# Precision_LPC_no_USB.net
KiCad netlist of a schematic drawn in EAGLE
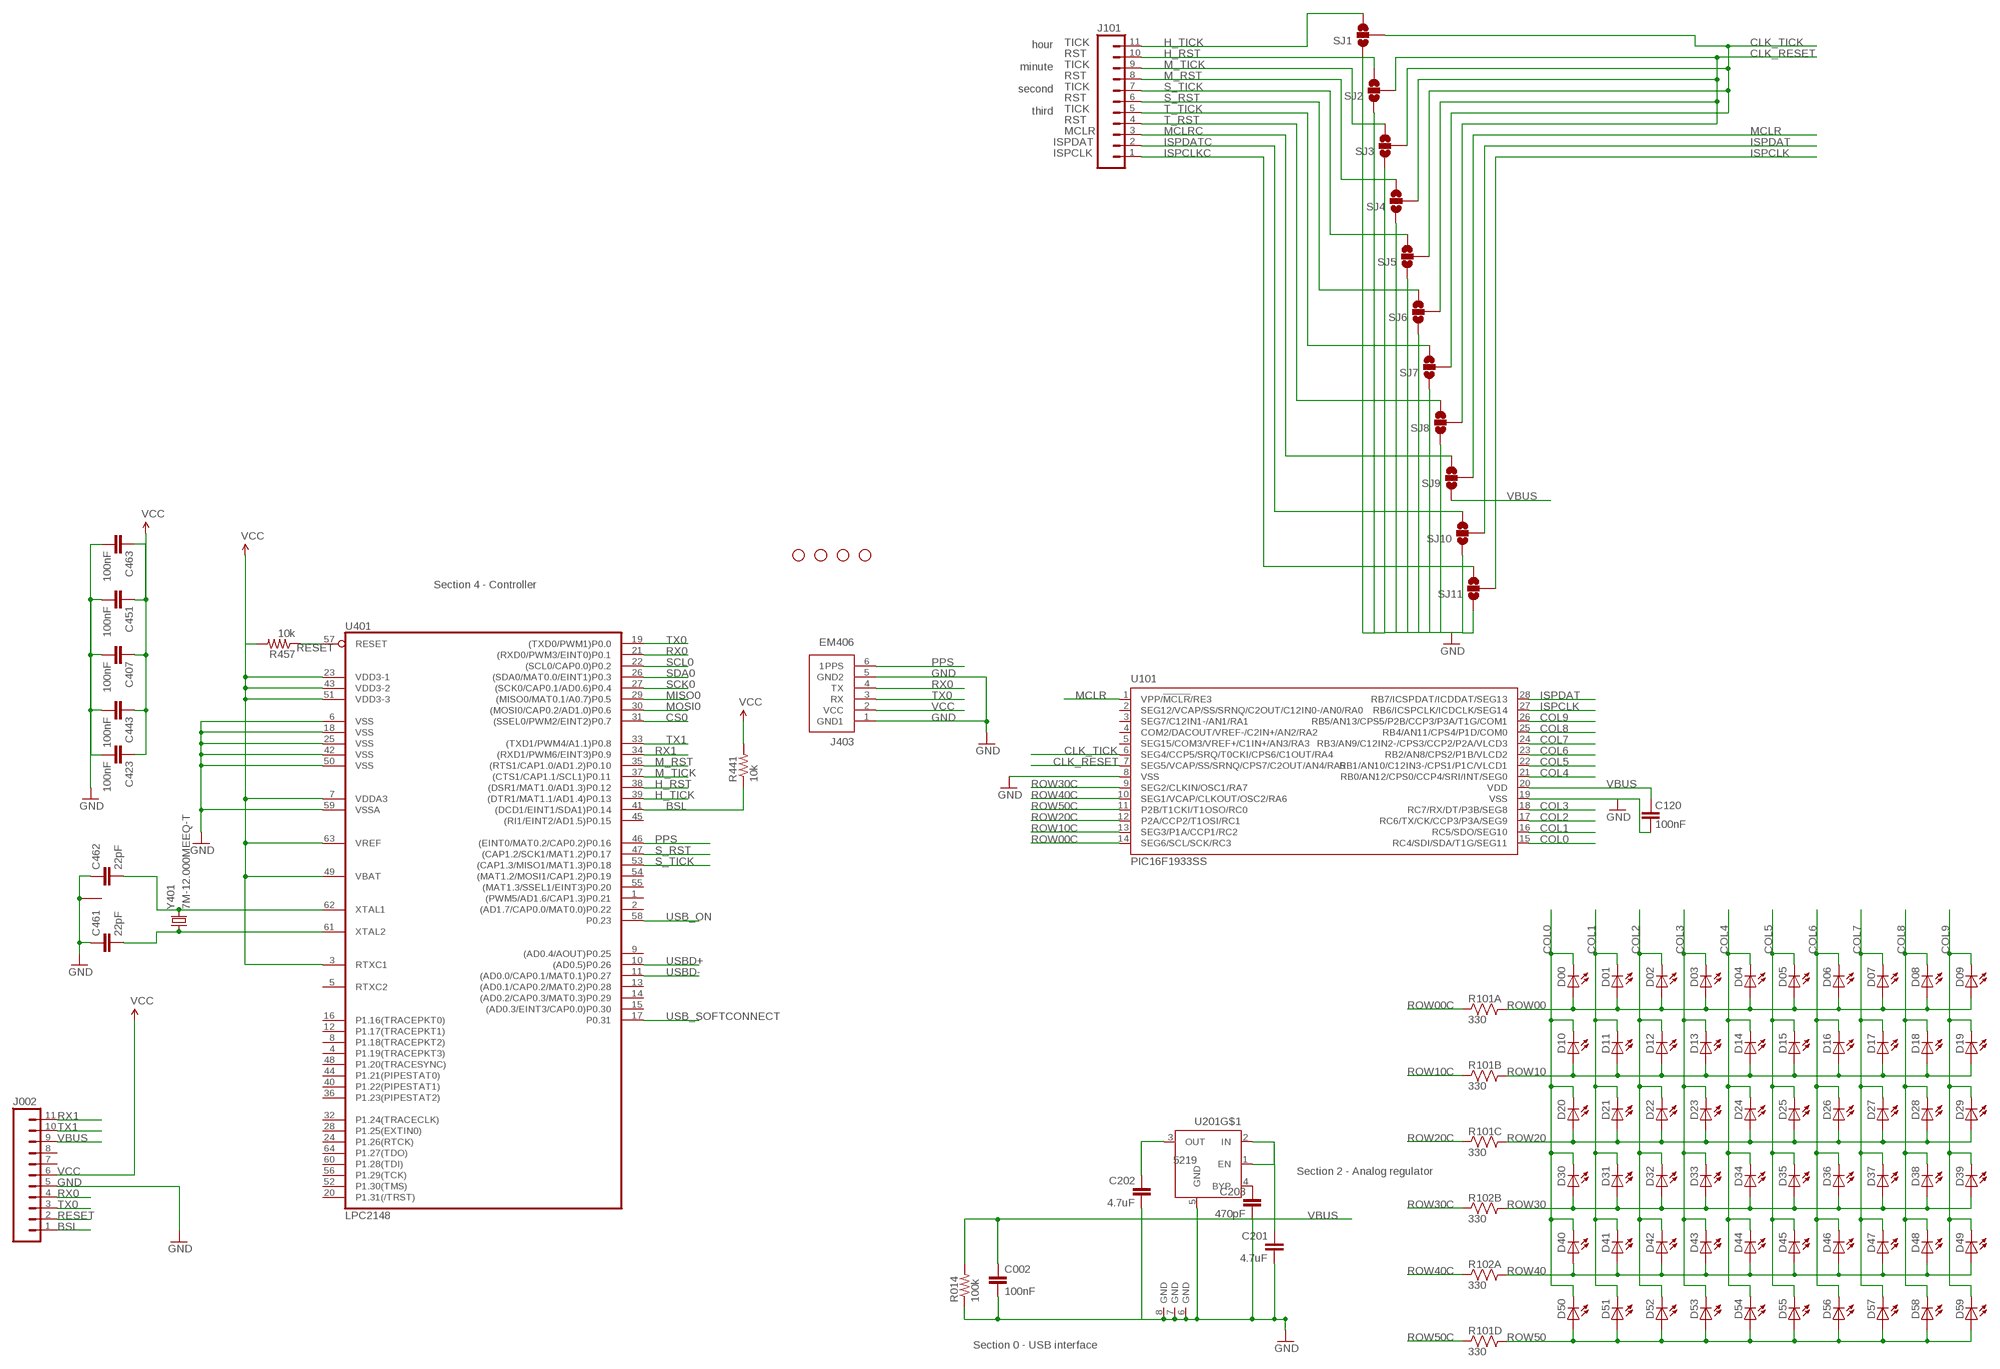
[diagram p0: schematic, sheet 1]

(export (version "E")
  (design (tool "Eeschema 10.0.6"))
  (components
    (comp (ref "C002")
      (value "100nF")
      (footprint "eagle-import:0402-CAP")
      (libsource (lib "eagle-import") (part "CAP0402-CAP"))
    )
    (comp (ref "C120")
      (value "100nF")
      (footprint "eagle-import:0402-CAP")
      (libsource (lib "eagle-import") (part "CAP0402-CAP"))
    )
    (comp (ref "C201")
      (value "4.7uF")
      (footprint "eagle-import:0402-CAP")
      (libsource (lib "eagle-import") (part "CAP0402-CAP"))
    )
    (comp (ref "C202")
      (value "4.7uF")
      (footprint "eagle-import:0402-CAP")
      (libsource (lib "eagle-import") (part "CAP0402-CAP"))
    )
    (comp (ref "C203")
      (value "470pF")
      (footprint "eagle-import:0402-CAP")
      (libsource (lib "eagle-import") (part "CAP0402-CAP"))
    )
    (comp (ref "C407")
      (value "100nF")
      (footprint "eagle-import:0402-CAP")
      (libsource (lib "eagle-import") (part "CAP0402-CAP"))
    )
    (comp (ref "C423")
      (value "100nF")
      (footprint "eagle-import:0402-CAP")
      (libsource (lib "eagle-import") (part "CAP0402-CAP"))
    )
    (comp (ref "C443")
      (value "100nF")
      (footprint "eagle-import:0402-CAP")
      (libsource (lib "eagle-import") (part "CAP0402-CAP"))
    )
    (comp (ref "C451")
      (value "100nF")
      (footprint "eagle-import:0402-CAP")
      (libsource (lib "eagle-import") (part "CAP0402-CAP"))
    )
    (comp (ref "C461")
      (value "22pF")
      (footprint "eagle-import:0402-CAP")
      (libsource (lib "eagle-import") (part "CAP0402-CAP"))
    )
    (comp (ref "C462")
      (value "22pF")
      (footprint "eagle-import:0402-CAP")
      (libsource (lib "eagle-import") (part "CAP0402-CAP"))
    )
    (comp (ref "C463")
      (value "100nF")
      (footprint "eagle-import:0402-CAP")
      (libsource (lib "eagle-import") (part "CAP0402-CAP"))
    )
    (comp (ref "D00")
      (value "LED3MM")
      (footprint "eagle-import:LED3MM")
      (libsource (lib "eagle-import") (part "LED3MM"))
    )
    (comp (ref "D01")
      (value "LED3MM")
      (footprint "eagle-import:LED3MM")
      (libsource (lib "eagle-import") (part "LED3MM"))
    )
    (comp (ref "D02")
      (value "LED3MM")
      (footprint "eagle-import:LED3MM")
      (libsource (lib "eagle-import") (part "LED3MM"))
    )
    (comp (ref "D03")
      (value "LED3MM")
      (footprint "eagle-import:LED3MM")
      (libsource (lib "eagle-import") (part "LED3MM"))
    )
    (comp (ref "D04")
      (value "LED3MM")
      (footprint "eagle-import:LED3MM")
      (libsource (lib "eagle-import") (part "LED3MM"))
    )
    (comp (ref "D05")
      (value "LED3MM")
      (footprint "eagle-import:LED3MM")
      (libsource (lib "eagle-import") (part "LED3MM"))
    )
    (comp (ref "D06")
      (value "LED3MM")
      (footprint "eagle-import:LED3MM")
      (libsource (lib "eagle-import") (part "LED3MM"))
    )
    (comp (ref "D07")
      (value "LED3MM")
      (footprint "eagle-import:LED3MM")
      (libsource (lib "eagle-import") (part "LED3MM"))
    )
    (comp (ref "D08")
      (value "LED3MM")
      (footprint "eagle-import:LED3MM")
      (libsource (lib "eagle-import") (part "LED3MM"))
    )
    (comp (ref "D09")
      (value "LED3MM")
      (footprint "eagle-import:LED3MM")
      (libsource (lib "eagle-import") (part "LED3MM"))
    )
    (comp (ref "D10")
      (value "LED3MM")
      (footprint "eagle-import:LED3MM")
      (libsource (lib "eagle-import") (part "LED3MM"))
    )
    (comp (ref "D11")
      (value "LED3MM")
      (footprint "eagle-import:LED3MM")
      (libsource (lib "eagle-import") (part "LED3MM"))
    )
    (comp (ref "D12")
      (value "LED3MM")
      (footprint "eagle-import:LED3MM")
      (libsource (lib "eagle-import") (part "LED3MM"))
    )
    (comp (ref "D13")
      (value "LED3MM")
      (footprint "eagle-import:LED3MM")
      (libsource (lib "eagle-import") (part "LED3MM"))
    )
    (comp (ref "D14")
      (value "LED3MM")
      (footprint "eagle-import:LED3MM")
      (libsource (lib "eagle-import") (part "LED3MM"))
    )
    (comp (ref "D15")
      (value "LED3MM")
      (footprint "eagle-import:LED3MM")
      (libsource (lib "eagle-import") (part "LED3MM"))
    )
    (comp (ref "D16")
      (value "LED3MM")
      (footprint "eagle-import:LED3MM")
      (libsource (lib "eagle-import") (part "LED3MM"))
    )
    (comp (ref "D17")
      (value "LED3MM")
      (footprint "eagle-import:LED3MM")
      (libsource (lib "eagle-import") (part "LED3MM"))
    )
    (comp (ref "D18")
      (value "LED3MM")
      (footprint "eagle-import:LED3MM")
      (libsource (lib "eagle-import") (part "LED3MM"))
    )
    (comp (ref "D19")
      (value "LED3MM")
      (footprint "eagle-import:LED3MM")
      (libsource (lib "eagle-import") (part "LED3MM"))
    )
    (comp (ref "D20")
      (value "LED3MM")
      (footprint "eagle-import:LED3MM")
      (libsource (lib "eagle-import") (part "LED3MM"))
    )
    (comp (ref "D21")
      (value "LED3MM")
      (footprint "eagle-import:LED3MM")
      (libsource (lib "eagle-import") (part "LED3MM"))
    )
    (comp (ref "D22")
      (value "LED3MM")
      (footprint "eagle-import:LED3MM")
      (libsource (lib "eagle-import") (part "LED3MM"))
    )
    (comp (ref "D23")
      (value "LED3MM")
      (footprint "eagle-import:LED3MM")
      (libsource (lib "eagle-import") (part "LED3MM"))
    )
    (comp (ref "D24")
      (value "LED3MM")
      (footprint "eagle-import:LED3MM")
      (libsource (lib "eagle-import") (part "LED3MM"))
    )
    (comp (ref "D25")
      (value "LED3MM")
      (footprint "eagle-import:LED3MM")
      (libsource (lib "eagle-import") (part "LED3MM"))
    )
    (comp (ref "D26")
      (value "LED3MM")
      (footprint "eagle-import:LED3MM")
      (libsource (lib "eagle-import") (part "LED3MM"))
    )
    (comp (ref "D27")
      (value "LED3MM")
      (footprint "eagle-import:LED3MM")
      (libsource (lib "eagle-import") (part "LED3MM"))
    )
    (comp (ref "D28")
      (value "LED3MM")
      (footprint "eagle-import:LED3MM")
      (libsource (lib "eagle-import") (part "LED3MM"))
    )
    (comp (ref "D29")
      (value "LED3MM")
      (footprint "eagle-import:LED3MM")
      (libsource (lib "eagle-import") (part "LED3MM"))
    )
    (comp (ref "D30")
      (value "LED3MM")
      (footprint "eagle-import:LED3MM")
      (libsource (lib "eagle-import") (part "LED3MM"))
    )
    (comp (ref "D31")
      (value "LED3MM")
      (footprint "eagle-import:LED3MM")
      (libsource (lib "eagle-import") (part "LED3MM"))
    )
    (comp (ref "D32")
      (value "LED3MM")
      (footprint "eagle-import:LED3MM")
      (libsource (lib "eagle-import") (part "LED3MM"))
    )
    (comp (ref "D33")
      (value "LED3MM")
      (footprint "eagle-import:LED3MM")
      (libsource (lib "eagle-import") (part "LED3MM"))
    )
    (comp (ref "D34")
      (value "LED3MM")
      (footprint "eagle-import:LED3MM")
      (libsource (lib "eagle-import") (part "LED3MM"))
    )
    (comp (ref "D35")
      (value "LED3MM")
      (footprint "eagle-import:LED3MM")
      (libsource (lib "eagle-import") (part "LED3MM"))
    )
    (comp (ref "D36")
      (value "LED3MM")
      (footprint "eagle-import:LED3MM")
      (libsource (lib "eagle-import") (part "LED3MM"))
    )
    (comp (ref "D37")
      (value "LED3MM")
      (footprint "eagle-import:LED3MM")
      (libsource (lib "eagle-import") (part "LED3MM"))
    )
    (comp (ref "D38")
      (value "LED3MM")
      (footprint "eagle-import:LED3MM")
      (libsource (lib "eagle-import") (part "LED3MM"))
    )
    (comp (ref "D39")
      (value "LED3MM")
      (footprint "eagle-import:LED3MM")
      (libsource (lib "eagle-import") (part "LED3MM"))
    )
    (comp (ref "D40")
      (value "LED3MM")
      (footprint "eagle-import:LED3MM")
      (libsource (lib "eagle-import") (part "LED3MM"))
    )
    (comp (ref "D41")
      (value "LED3MM")
      (footprint "eagle-import:LED3MM")
      (libsource (lib "eagle-import") (part "LED3MM"))
    )
    (comp (ref "D42")
      (value "LED3MM")
      (footprint "eagle-import:LED3MM")
      (libsource (lib "eagle-import") (part "LED3MM"))
    )
    (comp (ref "D43")
      (value "LED3MM")
      (footprint "eagle-import:LED3MM")
      (libsource (lib "eagle-import") (part "LED3MM"))
    )
    (comp (ref "D44")
      (value "LED3MM")
      (footprint "eagle-import:LED3MM")
      (libsource (lib "eagle-import") (part "LED3MM"))
    )
    (comp (ref "D45")
      (value "LED3MM")
      (footprint "eagle-import:LED3MM")
      (libsource (lib "eagle-import") (part "LED3MM"))
    )
    (comp (ref "D46")
      (value "LED3MM")
      (footprint "eagle-import:LED3MM")
      (libsource (lib "eagle-import") (part "LED3MM"))
    )
    (comp (ref "D47")
      (value "LED3MM")
      (footprint "eagle-import:LED3MM")
      (libsource (lib "eagle-import") (part "LED3MM"))
    )
    (comp (ref "D48")
      (value "LED3MM")
      (footprint "eagle-import:LED3MM")
      (libsource (lib "eagle-import") (part "LED3MM"))
    )
    (comp (ref "D49")
      (value "LED3MM")
      (footprint "eagle-import:LED3MM")
      (libsource (lib "eagle-import") (part "LED3MM"))
    )
    (comp (ref "D50")
      (value "LED3MM")
      (footprint "eagle-import:LED3MM")
      (libsource (lib "eagle-import") (part "LED3MM"))
    )
    (comp (ref "D51")
      (value "LED3MM")
      (footprint "eagle-import:LED3MM")
      (libsource (lib "eagle-import") (part "LED3MM"))
    )
    (comp (ref "D52")
      (value "LED3MM")
      (footprint "eagle-import:LED3MM")
      (libsource (lib "eagle-import") (part "LED3MM"))
    )
    (comp (ref "D53")
      (value "LED3MM")
      (footprint "eagle-import:LED3MM")
      (libsource (lib "eagle-import") (part "LED3MM"))
    )
    (comp (ref "D54")
      (value "LED3MM")
      (footprint "eagle-import:LED3MM")
      (libsource (lib "eagle-import") (part "LED3MM"))
    )
    (comp (ref "D55")
      (value "LED3MM")
      (footprint "eagle-import:LED3MM")
      (libsource (lib "eagle-import") (part "LED3MM"))
    )
    (comp (ref "D56")
      (value "LED3MM")
      (footprint "eagle-import:LED3MM")
      (libsource (lib "eagle-import") (part "LED3MM"))
    )
    (comp (ref "D57")
      (value "LED3MM")
      (footprint "eagle-import:LED3MM")
      (libsource (lib "eagle-import") (part "LED3MM"))
    )
    (comp (ref "D58")
      (value "LED3MM")
      (footprint "eagle-import:LED3MM")
      (libsource (lib "eagle-import") (part "LED3MM"))
    )
    (comp (ref "D59")
      (value "LED3MM")
      (footprint "eagle-import:LED3MM")
      (libsource (lib "eagle-import") (part "LED3MM"))
    )
    (comp (ref "J002")
      (value "M11PTH")
      (footprint "eagle-import:1X11")
      (libsource (lib "eagle-import") (part "M11PTH"))
    )
    (comp (ref "J101")
      (value "M11PTH")
      (footprint "eagle-import:1X11")
      (libsource (lib "eagle-import") (part "M11PTH"))
    )
    (comp (ref "J403")
      (value "EM406")
      (footprint "eagle-import:EM406@1")
      (libsource (lib "eagle-import") (part "EM406"))
    )
    (comp (ref "JP3")
      (value "STAND-OFF")
      (footprint "eagle-import:STAND-OFF")
      (libsource (lib "eagle-import") (part "STAND-OFF"))
    )
    (comp (ref "JP4")
      (value "STAND-OFF")
      (footprint "eagle-import:STAND-OFF")
      (libsource (lib "eagle-import") (part "STAND-OFF"))
    )
    (comp (ref "JP5")
      (value "STAND-OFF")
      (footprint "eagle-import:STAND-OFF")
      (libsource (lib "eagle-import") (part "STAND-OFF"))
    )
    (comp (ref "JP6")
      (value "STAND-OFF")
      (footprint "eagle-import:STAND-OFF")
      (libsource (lib "eagle-import") (part "STAND-OFF"))
    )
    (comp (ref "R014")
      (value "100k")
      (footprint "eagle-import:0402-RES")
      (libsource (lib "eagle-import") (part "RESISTOR0402-RES"))
    )
    (comp (ref "R101")
      (value "330")
      (footprint "eagle-import:CRA06")
      (libsource (lib "eagle-import") (part "CRA06S-8"))
    )
    (comp (ref "R102")
      (value "330")
      (footprint "eagle-import:CRA06")
      (libsource (lib "eagle-import") (part "CRA06S-8"))
    )
    (comp (ref "R441")
      (value "10k")
      (footprint "eagle-import:0402-RES")
      (libsource (lib "eagle-import") (part "RESISTOR0402-RES"))
    )
    (comp (ref "R457")
      (value "10k")
      (footprint "eagle-import:0402-RES")
      (libsource (lib "eagle-import") (part "RESISTOR0402-RES"))
    )
    (comp (ref "SJ1")
      (value "SOLDERJUMPER_2WAYS")
      (footprint "eagle-import:SJ_3")
      (libsource (lib "eagle-import") (part "SOLDERJUMPER_2WAYS"))
    )
    (comp (ref "SJ2")
      (value "SOLDERJUMPER_2WAYS")
      (footprint "eagle-import:SJ_3")
      (libsource (lib "eagle-import") (part "SOLDERJUMPER_2WAYS"))
    )
    (comp (ref "SJ3")
      (value "SOLDERJUMPER_2WAYS")
      (footprint "eagle-import:SJ_3")
      (libsource (lib "eagle-import") (part "SOLDERJUMPER_2WAYS"))
    )
    (comp (ref "SJ4")
      (value "SOLDERJUMPER_2WAYS")
      (footprint "eagle-import:SJ_3")
      (libsource (lib "eagle-import") (part "SOLDERJUMPER_2WAYS"))
    )
    (comp (ref "SJ5")
      (value "SOLDERJUMPER_2WAYS")
      (footprint "eagle-import:SJ_3")
      (libsource (lib "eagle-import") (part "SOLDERJUMPER_2WAYS"))
    )
    (comp (ref "SJ6")
      (value "SOLDERJUMPER_2WAYS")
      (footprint "eagle-import:SJ_3")
      (libsource (lib "eagle-import") (part "SOLDERJUMPER_2WAYS"))
    )
    (comp (ref "SJ7")
      (value "SOLDERJUMPER_2WAYS")
      (footprint "eagle-import:SJ_3")
      (libsource (lib "eagle-import") (part "SOLDERJUMPER_2WAYS"))
    )
    (comp (ref "SJ8")
      (value "SOLDERJUMPER_2WAYS")
      (footprint "eagle-import:SJ_3")
      (libsource (lib "eagle-import") (part "SOLDERJUMPER_2WAYS"))
    )
    (comp (ref "SJ9")
      (value "SOLDERJUMPER_2WAYS")
      (footprint "eagle-import:SJ_3")
      (libsource (lib "eagle-import") (part "SOLDERJUMPER_2WAYS"))
    )
    (comp (ref "SJ10")
      (value "SOLDERJUMPER_2WAYS")
      (footprint "eagle-import:SJ_3")
      (libsource (lib "eagle-import") (part "SOLDERJUMPER_2WAYS"))
    )
    (comp (ref "SJ11")
      (value "SOLDERJUMPER_2WAYS")
      (footprint "eagle-import:SJ_3")
      (libsource (lib "eagle-import") (part "SOLDERJUMPER_2WAYS"))
    )
    (comp (ref "U101")
      (value "PIC16F1933SS")
      (footprint "eagle-import:SSOP28")
      (fields (field (name "MPN") "PIC16F1933T-I/SS"))
      (libsource (lib "eagle-import") (part "PIC16F19SS33"))
    )
    (comp (ref "U201")
      (value "5219")
      (footprint "eagle-import:MSOP08")
      (libsource (lib "eagle-import") (part "MIC5219FMM"))
    )
    (comp (ref "U401")
      (value "LPC2148")
      (footprint "eagle-import:SQFP-S-10X10-64")
      (libsource (lib "eagle-import") (part "LPC213X"))
    )
    (comp (ref "Y401")
      (value "7M-12.000MEEQ-T")
      (footprint "eagle-import:CRYSTAL_SMD")
      (libsource (lib "eagle-import") (part "TSX-3225"))
    )
  )
  (nets
    (net (code "1") (name "/BSL") (class "Default")
      (node (ref "J002") (pin "1") (pinfunction "1_1") (pintype "passive"))
      (node (ref "R441") (pin "1") (pinfunction "1_1") (pintype "passive"))
      (node (ref "U401") (pin "41") (pinfunction "(DCD1/EINT1/SDA1)P0.14_41") (pintype "bidirectional"))
    )
    (net (code "2") (name "/CLK_RESET") (class "Default")
      (node (ref "SJ2") (pin "2") (pinfunction "2_2") (pintype "passive"))
      (node (ref "SJ4") (pin "2") (pinfunction "2_2") (pintype "passive"))
      (node (ref "SJ6") (pin "2") (pinfunction "2_2") (pintype "passive"))
      (node (ref "SJ8") (pin "2") (pinfunction "2_2") (pintype "passive"))
      (node (ref "U101") (pin "7") (pinfunction "SEG5/VCAP/SS/SRNQ/CPS7/C2OUT/AN4/RA5_7") (pintype "bidirectional"))
    )
    (net (code "3") (name "/CLK_TICK") (class "Default")
      (node (ref "SJ1") (pin "2") (pinfunction "2_2") (pintype "passive"))
      (node (ref "SJ3") (pin "2") (pinfunction "2_2") (pintype "passive"))
      (node (ref "SJ5") (pin "2") (pinfunction "2_2") (pintype "passive"))
      (node (ref "SJ7") (pin "2") (pinfunction "2_2") (pintype "passive"))
      (node (ref "U101") (pin "6") (pinfunction "SEG4/CCP5/SRQ/T0CKI/CPS6/C1OUT/RA4_6") (pintype "bidirectional"))
    )
    (net (code "4") (name "/COL0") (class "Default")
      (node (ref "D00") (pin "K") (pinfunction "C_K") (pintype "passive"))
      (node (ref "D10") (pin "K") (pinfunction "C_K") (pintype "passive"))
      (node (ref "D20") (pin "K") (pinfunction "C_K") (pintype "passive"))
      (node (ref "D30") (pin "K") (pinfunction "C_K") (pintype "passive"))
      (node (ref "D40") (pin "K") (pinfunction "C_K") (pintype "passive"))
      (node (ref "D50") (pin "K") (pinfunction "C_K") (pintype "passive"))
      (node (ref "U101") (pin "15") (pinfunction "RC4/SDI/SDA/T1G/SEG11_15") (pintype "bidirectional"))
    )
    (net (code "5") (name "/COL1") (class "Default")
      (node (ref "D01") (pin "K") (pinfunction "C_K") (pintype "passive"))
      (node (ref "D11") (pin "K") (pinfunction "C_K") (pintype "passive"))
      (node (ref "D21") (pin "K") (pinfunction "C_K") (pintype "passive"))
      (node (ref "D31") (pin "K") (pinfunction "C_K") (pintype "passive"))
      (node (ref "D41") (pin "K") (pinfunction "C_K") (pintype "passive"))
      (node (ref "D51") (pin "K") (pinfunction "C_K") (pintype "passive"))
      (node (ref "U101") (pin "16") (pinfunction "RC5/SDO/SEG10_16") (pintype "bidirectional"))
    )
    (net (code "6") (name "/COL2") (class "Default")
      (node (ref "D02") (pin "K") (pinfunction "C_K") (pintype "passive"))
      (node (ref "D12") (pin "K") (pinfunction "C_K") (pintype "passive"))
      (node (ref "D22") (pin "K") (pinfunction "C_K") (pintype "passive"))
      (node (ref "D32") (pin "K") (pinfunction "C_K") (pintype "passive"))
      (node (ref "D42") (pin "K") (pinfunction "C_K") (pintype "passive"))
      (node (ref "D52") (pin "K") (pinfunction "C_K") (pintype "passive"))
      (node (ref "U101") (pin "17") (pinfunction "RC6/TX/CK/CCP3/P3A/SEG9_17") (pintype "bidirectional"))
    )
    (net (code "7") (name "/COL3") (class "Default")
      (node (ref "D03") (pin "K") (pinfunction "C_K") (pintype "passive"))
      (node (ref "D13") (pin "K") (pinfunction "C_K") (pintype "passive"))
      (node (ref "D23") (pin "K") (pinfunction "C_K") (pintype "passive"))
      (node (ref "D33") (pin "K") (pinfunction "C_K") (pintype "passive"))
      (node (ref "D43") (pin "K") (pinfunction "C_K") (pintype "passive"))
      (node (ref "D53") (pin "K") (pinfunction "C_K") (pintype "passive"))
      (node (ref "U101") (pin "18") (pinfunction "RC7/RX/DT/P3B/SEG8_18") (pintype "bidirectional"))
    )
    (net (code "8") (name "/COL4") (class "Default")
      (node (ref "D04") (pin "K") (pinfunction "C_K") (pintype "passive"))
      (node (ref "D14") (pin "K") (pinfunction "C_K") (pintype "passive"))
      (node (ref "D24") (pin "K") (pinfunction "C_K") (pintype "passive"))
      (node (ref "D34") (pin "K") (pinfunction "C_K") (pintype "passive"))
      (node (ref "D44") (pin "K") (pinfunction "C_K") (pintype "passive"))
      (node (ref "D54") (pin "K") (pinfunction "C_K") (pintype "passive"))
      (node (ref "U101") (pin "21") (pinfunction "RB0/AN12/CPS0/CCP4/SRI/INT/SEG0_21") (pintype "bidirectional"))
    )
    (net (code "9") (name "/COL5") (class "Default")
      (node (ref "D05") (pin "K") (pinfunction "C_K") (pintype "passive"))
      (node (ref "D15") (pin "K") (pinfunction "C_K") (pintype "passive"))
      (node (ref "D25") (pin "K") (pinfunction "C_K") (pintype "passive"))
      (node (ref "D35") (pin "K") (pinfunction "C_K") (pintype "passive"))
      (node (ref "D45") (pin "K") (pinfunction "C_K") (pintype "passive"))
      (node (ref "D55") (pin "K") (pinfunction "C_K") (pintype "passive"))
      (node (ref "U101") (pin "22") (pinfunction "RB1/AN10/C12IN3-/CPS1/P1C/VLCD1_22") (pintype "bidirectional"))
    )
    (net (code "10") (name "/COL6") (class "Default")
      (node (ref "D06") (pin "K") (pinfunction "C_K") (pintype "passive"))
      (node (ref "D16") (pin "K") (pinfunction "C_K") (pintype "passive"))
      (node (ref "D26") (pin "K") (pinfunction "C_K") (pintype "passive"))
      (node (ref "D36") (pin "K") (pinfunction "C_K") (pintype "passive"))
      (node (ref "D46") (pin "K") (pinfunction "C_K") (pintype "passive"))
      (node (ref "D56") (pin "K") (pinfunction "C_K") (pintype "passive"))
      (node (ref "U101") (pin "23") (pinfunction "RB2/AN8/CPS2/P1B/VLCD2_23") (pintype "bidirectional"))
    )
    (net (code "11") (name "/COL7") (class "Default")
      (node (ref "D07") (pin "K") (pinfunction "C_K") (pintype "passive"))
      (node (ref "D17") (pin "K") (pinfunction "C_K") (pintype "passive"))
      (node (ref "D27") (pin "K") (pinfunction "C_K") (pintype "passive"))
      (node (ref "D37") (pin "K") (pinfunction "C_K") (pintype "passive"))
      (node (ref "D47") (pin "K") (pinfunction "C_K") (pintype "passive"))
      (node (ref "D57") (pin "K") (pinfunction "C_K") (pintype "passive"))
      (node (ref "U101") (pin "24") (pinfunction "RB3/AN9/C12IN2-/CPS3/CCP2/P2A/VLCD3_24") (pintype "bidirectional"))
    )
    (net (code "12") (name "/COL8") (class "Default")
      (node (ref "D08") (pin "K") (pinfunction "C_K") (pintype "passive"))
      (node (ref "D18") (pin "K") (pinfunction "C_K") (pintype "passive"))
      (node (ref "D28") (pin "K") (pinfunction "C_K") (pintype "passive"))
      (node (ref "D38") (pin "K") (pinfunction "C_K") (pintype "passive"))
      (node (ref "D48") (pin "K") (pinfunction "C_K") (pintype "passive"))
      (node (ref "D58") (pin "K") (pinfunction "C_K") (pintype "passive"))
      (node (ref "U101") (pin "25") (pinfunction "RB4/AN11/CPS4/P1D/COM0_25") (pintype "bidirectional"))
    )
    (net (code "13") (name "/COL9") (class "Default")
      (node (ref "D09") (pin "K") (pinfunction "C_K") (pintype "passive"))
      (node (ref "D19") (pin "K") (pinfunction "C_K") (pintype "passive"))
      (node (ref "D29") (pin "K") (pinfunction "C_K") (pintype "passive"))
      (node (ref "D39") (pin "K") (pinfunction "C_K") (pintype "passive"))
      (node (ref "D49") (pin "K") (pinfunction "C_K") (pintype "passive"))
      (node (ref "D59") (pin "K") (pinfunction "C_K") (pintype "passive"))
      (node (ref "U101") (pin "26") (pinfunction "RB5/AN13/CPS5/P2B/CCP3/P3A/T1G/COM1_26") (pintype "bidirectional"))
    )
    (net (code "14") (name "/CS0") (class "Default")
      (node (ref "U401") (pin "31") (pinfunction "(SSEL0/PWM2/EINT2)P0.7_31") (pintype "bidirectional"))
    )
    (net (code "15") (name "/H_RST") (class "Default")
      (node (ref "J101") (pin "10") (pinfunction "10_10") (pintype "passive"))
      (node (ref "SJ2") (pin "3") (pinfunction "3_3") (pintype "passive"))
      (node (ref "U401") (pin "38") (pinfunction "(DSR1/MAT1.0/AD1.3)P0.12_38") (pintype "bidirectional"))
    )
    (net (code "16") (name "/H_TICK") (class "Default")
      (node (ref "J101") (pin "11") (pinfunction "11_11") (pintype "passive"))
      (node (ref "SJ1") (pin "3") (pinfunction "3_3") (pintype "passive"))
      (node (ref "U401") (pin "39") (pinfunction "(DTR1/MAT1.1/AD1.4)P0.13_39") (pintype "bidirectional"))
    )
    (net (code "17") (name "/ISPCLK") (class "Default")
      (node (ref "SJ11") (pin "2") (pinfunction "2_2") (pintype "passive"))
      (node (ref "U101") (pin "27") (pinfunction "RB6/ICSPCLK/ICDCLK/SEG14_27") (pintype "bidirectional"))
    )
    (net (code "18") (name "/ISPCLKC") (class "Default")
      (node (ref "J101") (pin "1") (pinfunction "1_1") (pintype "passive"))
      (node (ref "SJ11") (pin "3") (pinfunction "3_3") (pintype "passive"))
    )
    (net (code "19") (name "/ISPDAT") (class "Default")
      (node (ref "SJ10") (pin "2") (pinfunction "2_2") (pintype "passive"))
      (node (ref "U101") (pin "28") (pinfunction "RB7/ICSPDAT/ICDDAT/SEG13_28") (pintype "bidirectional"))
    )
    (net (code "20") (name "/ISPDATC") (class "Default")
      (node (ref "J101") (pin "2") (pinfunction "2_2") (pintype "passive"))
      (node (ref "SJ10") (pin "3") (pinfunction "3_3") (pintype "passive"))
    )
    (net (code "21") (name "/MCLR") (class "Default")
      (node (ref "SJ9") (pin "2") (pinfunction "2_2") (pintype "passive"))
      (node (ref "U101") (pin "1") (pinfunction "VPP/~{MCLR}/RE3_1") (pintype "input"))
    )
    (net (code "22") (name "/MCLRC") (class "Default")
      (node (ref "J101") (pin "3") (pinfunction "3_3") (pintype "passive"))
      (node (ref "SJ9") (pin "3") (pinfunction "3_3") (pintype "passive"))
    )
    (net (code "23") (name "/MISO0") (class "Default")
      (node (ref "U401") (pin "29") (pinfunction "(MISO0/MAT0.1/A0.7)P0.5_29") (pintype "bidirectional"))
    )
    (net (code "24") (name "/MOSI0") (class "Default")
      (node (ref "U401") (pin "30") (pinfunction "(MOSI0/CAP0.2/AD1.0)P0.6_30") (pintype "bidirectional"))
    )
    (net (code "25") (name "/M_RST") (class "Default")
      (node (ref "J101") (pin "8") (pinfunction "8_8") (pintype "passive"))
      (node (ref "SJ4") (pin "3") (pinfunction "3_3") (pintype "passive"))
      (node (ref "U401") (pin "35") (pinfunction "(RTS1/CAP1.0/AD1.2)P0.10_35") (pintype "bidirectional"))
    )
    (net (code "26") (name "/M_TICK") (class "Default")
      (node (ref "J101") (pin "9") (pinfunction "9_9") (pintype "passive"))
      (node (ref "SJ3") (pin "3") (pinfunction "3_3") (pintype "passive"))
      (node (ref "U401") (pin "37") (pinfunction "(CTS1/CAP1.1/SCL1)P0.11_37") (pintype "bidirectional"))
    )
    (net (code "27") (name "/PPS") (class "Default")
      (node (ref "J403") (pin "6") (pinfunction "1PPS_6") (pintype "bidirectional"))
      (node (ref "U401") (pin "46") (pinfunction "(EINT0/MAT0.2/CAP0.2)P0.16_46") (pintype "bidirectional"))
    )
    (net (code "28") (name "/RESET") (class "Default")
      (node (ref "J002") (pin "2") (pinfunction "2_2") (pintype "passive"))
      (node (ref "R457") (pin "1") (pinfunction "1_1") (pintype "passive"))
      (node (ref "U401") (pin "57") (pinfunction "RESET_57") (pintype "input"))
    )
    (net (code "29") (name "/ROW00") (class "Default")
      (node (ref "D00") (pin "A") (pinfunction "A_A") (pintype "passive"))
      (node (ref "D01") (pin "A") (pinfunction "A_A") (pintype "passive"))
      (node (ref "D02") (pin "A") (pinfunction "A_A") (pintype "passive"))
      (node (ref "D03") (pin "A") (pinfunction "A_A") (pintype "passive"))
      (node (ref "D04") (pin "A") (pinfunction "A_A") (pintype "passive"))
      (node (ref "D05") (pin "A") (pinfunction "A_A") (pintype "passive"))
      (node (ref "D06") (pin "A") (pinfunction "A_A") (pintype "passive"))
      (node (ref "D07") (pin "A") (pinfunction "A_A") (pintype "passive"))
      (node (ref "D08") (pin "A") (pinfunction "A_A") (pintype "passive"))
      (node (ref "D09") (pin "A") (pinfunction "A_A") (pintype "passive"))
      (node (ref "R101") (pin "8") (pinfunction "2_8") (pintype "passive"))
    )
    (net (code "30") (name "/ROW00C") (class "Default")
      (node (ref "R101") (pin "1") (pinfunction "1_1") (pintype "passive"))
      (node (ref "U101") (pin "14") (pinfunction "SEG6/SCL/SCK/RC3_14") (pintype "bidirectional"))
    )
    (net (code "31") (name "/ROW10") (class "Default")
      (node (ref "D10") (pin "A") (pinfunction "A_A") (pintype "passive"))
      (node (ref "D11") (pin "A") (pinfunction "A_A") (pintype "passive"))
      (node (ref "D12") (pin "A") (pinfunction "A_A") (pintype "passive"))
      (node (ref "D13") (pin "A") (pinfunction "A_A") (pintype "passive"))
      (node (ref "D14") (pin "A") (pinfunction "A_A") (pintype "passive"))
      (node (ref "D15") (pin "A") (pinfunction "A_A") (pintype "passive"))
      (node (ref "D16") (pin "A") (pinfunction "A_A") (pintype "passive"))
      (node (ref "D17") (pin "A") (pinfunction "A_A") (pintype "passive"))
      (node (ref "D18") (pin "A") (pinfunction "A_A") (pintype "passive"))
      (node (ref "D19") (pin "A") (pinfunction "A_A") (pintype "passive"))
      (node (ref "R101") (pin "7") (pinfunction "2_7") (pintype "passive"))
    )
    (net (code "32") (name "/ROW10C") (class "Default")
      (node (ref "R101") (pin "2") (pinfunction "1_2") (pintype "passive"))
      (node (ref "U101") (pin "13") (pinfunction "SEG3/P1A/CCP1/RC2_13") (pintype "bidirectional"))
    )
    (net (code "33") (name "/ROW20") (class "Default")
      (node (ref "D20") (pin "A") (pinfunction "A_A") (pintype "passive"))
      (node (ref "D21") (pin "A") (pinfunction "A_A") (pintype "passive"))
      (node (ref "D22") (pin "A") (pinfunction "A_A") (pintype "passive"))
      (node (ref "D23") (pin "A") (pinfunction "A_A") (pintype "passive"))
      (node (ref "D24") (pin "A") (pinfunction "A_A") (pintype "passive"))
      (node (ref "D25") (pin "A") (pinfunction "A_A") (pintype "passive"))
      (node (ref "D26") (pin "A") (pinfunction "A_A") (pintype "passive"))
      (node (ref "D27") (pin "A") (pinfunction "A_A") (pintype "passive"))
      (node (ref "D28") (pin "A") (pinfunction "A_A") (pintype "passive"))
      (node (ref "D29") (pin "A") (pinfunction "A_A") (pintype "passive"))
      (node (ref "R101") (pin "6") (pinfunction "2_6") (pintype "passive"))
    )
    (net (code "34") (name "/ROW20C") (class "Default")
      (node (ref "R101") (pin "3") (pinfunction "1_3") (pintype "passive"))
      (node (ref "U101") (pin "12") (pinfunction "P2A/CCP2/T1OSI/RC1_12") (pintype "bidirectional"))
    )
    (net (code "35") (name "/ROW30") (class "Default")
      (node (ref "D30") (pin "A") (pinfunction "A_A") (pintype "passive"))
      (node (ref "D31") (pin "A") (pinfunction "A_A") (pintype "passive"))
      (node (ref "D32") (pin "A") (pinfunction "A_A") (pintype "passive"))
      (node (ref "D33") (pin "A") (pinfunction "A_A") (pintype "passive"))
      (node (ref "D34") (pin "A") (pinfunction "A_A") (pintype "passive"))
      (node (ref "D35") (pin "A") (pinfunction "A_A") (pintype "passive"))
      (node (ref "D36") (pin "A") (pinfunction "A_A") (pintype "passive"))
      (node (ref "D37") (pin "A") (pinfunction "A_A") (pintype "passive"))
      (node (ref "D38") (pin "A") (pinfunction "A_A") (pintype "passive"))
      (node (ref "D39") (pin "A") (pinfunction "A_A") (pintype "passive"))
      (node (ref "R102") (pin "7") (pinfunction "2_7") (pintype "passive"))
    )
    (net (code "36") (name "/ROW30C") (class "Default")
      (node (ref "R102") (pin "2") (pinfunction "1_2") (pintype "passive"))
      (node (ref "U101") (pin "9") (pinfunction "SEG2/CLKIN/OSC1/RA7_9") (pintype "bidirectional"))
    )
    (net (code "37") (name "/ROW40") (class "Default")
      (node (ref "D40") (pin "A") (pinfunction "A_A") (pintype "passive"))
      (node (ref "D41") (pin "A") (pinfunction "A_A") (pintype "passive"))
      (node (ref "D42") (pin "A") (pinfunction "A_A") (pintype "passive"))
      (node (ref "D43") (pin "A") (pinfunction "A_A") (pintype "passive"))
      (node (ref "D44") (pin "A") (pinfunction "A_A") (pintype "passive"))
      (node (ref "D45") (pin "A") (pinfunction "A_A") (pintype "passive"))
      (node (ref "D46") (pin "A") (pinfunction "A_A") (pintype "passive"))
      (node (ref "D47") (pin "A") (pinfunction "A_A") (pintype "passive"))
      (node (ref "D48") (pin "A") (pinfunction "A_A") (pintype "passive"))
      (node (ref "D49") (pin "A") (pinfunction "A_A") (pintype "passive"))
      (node (ref "R102") (pin "8") (pinfunction "2_8") (pintype "passive"))
    )
    (net (code "38") (name "/ROW40C") (class "Default")
      (node (ref "R102") (pin "1") (pinfunction "1_1") (pintype "passive"))
      (node (ref "U101") (pin "10") (pinfunction "SEG1/VCAP/CLKOUT/OSC2/RA6_10") (pintype "bidirectional"))
    )
    (net (code "39") (name "/ROW50") (class "Default")
      (node (ref "D50") (pin "A") (pinfunction "A_A") (pintype "passive"))
      (node (ref "D51") (pin "A") (pinfunction "A_A") (pintype "passive"))
      (node (ref "D52") (pin "A") (pinfunction "A_A") (pintype "passive"))
      (node (ref "D53") (pin "A") (pinfunction "A_A") (pintype "passive"))
      (node (ref "D54") (pin "A") (pinfunction "A_A") (pintype "passive"))
      (node (ref "D55") (pin "A") (pinfunction "A_A") (pintype "passive"))
      (node (ref "D56") (pin "A") (pinfunction "A_A") (pintype "passive"))
      (node (ref "D57") (pin "A") (pinfunction "A_A") (pintype "passive"))
      (node (ref "D58") (pin "A") (pinfunction "A_A") (pintype "passive"))
      (node (ref "D59") (pin "A") (pinfunction "A_A") (pintype "passive"))
      (node (ref "R101") (pin "5") (pinfunction "2_5") (pintype "passive"))
    )
    (net (code "40") (name "/ROW50C") (class "Default")
      (node (ref "R101") (pin "4") (pinfunction "1_4") (pintype "passive"))
      (node (ref "U101") (pin "11") (pinfunction "P2B/T1CKI/T1OSO/RC0_11") (pintype "bidirectional"))
    )
    (net (code "41") (name "/RX0") (class "Default")
      (node (ref "J002") (pin "4") (pinfunction "4_4") (pintype "passive"))
      (node (ref "J403") (pin "4") (pinfunction "TX_4") (pintype "bidirectional"))
      (node (ref "U401") (pin "21") (pinfunction "(RXD0/PWM3/EINT0)P0.1_21") (pintype "bidirectional"))
    )
    (net (code "42") (name "/RX1") (class "Default")
      (node (ref "J002") (pin "11") (pinfunction "11_11") (pintype "passive"))
      (node (ref "U401") (pin "34") (pinfunction "(RXD1/PWM6/EINT3)P0.9_34") (pintype "bidirectional"))
    )
    (net (code "43") (name "/SCK0") (class "Default")
      (node (ref "U401") (pin "27") (pinfunction "(SCK0/CAP0.1/AD0.6)P0.4_27") (pintype "bidirectional"))
    )
    (net (code "44") (name "/SCL0") (class "Default")
      (node (ref "U401") (pin "22") (pinfunction "(SCL0/CAP0.0)P0.2_22") (pintype "bidirectional"))
    )
    (net (code "45") (name "/SDA0") (class "Default")
      (node (ref "U401") (pin "26") (pinfunction "(SDA0/MAT0.0/EINT1)P0.3_26") (pintype "bidirectional"))
    )
    (net (code "46") (name "/S_RST") (class "Default")
      (node (ref "J101") (pin "6") (pinfunction "6_6") (pintype "passive"))
      (node (ref "SJ6") (pin "3") (pinfunction "3_3") (pintype "passive"))
      (node (ref "U401") (pin "47") (pinfunction "(CAP1.2/SCK1/MAT1.2)P0.17_47") (pintype "bidirectional"))
    )
    (net (code "47") (name "/S_TICK") (class "Default")
      (node (ref "J101") (pin "7") (pinfunction "7_7") (pintype "passive"))
      (node (ref "SJ5") (pin "3") (pinfunction "3_3") (pintype "passive"))
      (node (ref "U401") (pin "53") (pinfunction "(CAP1.3/MISO1/MAT1.3)P0.18_53") (pintype "bidirectional"))
    )
    (net (code "48") (name "/TX0") (class "Default")
      (node (ref "J002") (pin "3") (pinfunction "3_3") (pintype "passive"))
      (node (ref "J403") (pin "3") (pinfunction "RX_3") (pintype "bidirectional"))
      (node (ref "U401") (pin "19") (pinfunction "(TXD0/PWM1)P0.0_19") (pintype "bidirectional"))
    )
    (net (code "49") (name "/TX1") (class "Default")
      (node (ref "J002") (pin "10") (pinfunction "10_10") (pintype "passive"))
      (node (ref "U401") (pin "33") (pinfunction "(TXD1/PWM4/A1.1)P0.8_33") (pintype "bidirectional"))
    )
    (net (code "50") (name "/T_RST") (class "Default")
      (node (ref "J101") (pin "4") (pinfunction "4_4") (pintype "passive"))
      (node (ref "SJ8") (pin "3") (pinfunction "3_3") (pintype "passive"))
    )
    (net (code "51") (name "/T_TICK") (class "Default")
      (node (ref "J101") (pin "5") (pinfunction "5_5") (pintype "passive"))
      (node (ref "SJ7") (pin "3") (pinfunction "3_3") (pintype "passive"))
    )
    (net (code "52") (name "/USBD+") (class "Default")
      (node (ref "U401") (pin "10") (pinfunction "(AD0.5)P0.26_10") (pintype "bidirectional"))
    )
    (net (code "53") (name "/USBD-") (class "Default")
      (node (ref "U401") (pin "11") (pinfunction "(AD0.0/CAP0.1/MAT0.1)P0.27_11") (pintype "bidirectional"))
    )
    (net (code "54") (name "/USB_ON") (class "Default")
      (node (ref "U401") (pin "58") (pinfunction "P0.23_58") (pintype "bidirectional"))
    )
    (net (code "55") (name "/USB_SOFTCONNECT") (class "Default")
      (node (ref "U401") (pin "17") (pinfunction "P0.31_17") (pintype "output"))
    )
    (net (code "56") (name "/VBUS") (class "Default")
      (node (ref "C002") (pin "1") (pinfunction "1_1") (pintype "passive"))
      (node (ref "C120") (pin "2") (pinfunction "2_2") (pintype "passive"))
      (node (ref "C201") (pin "1") (pinfunction "1_1") (pintype "passive"))
      (node (ref "J002") (pin "9") (pinfunction "9_9") (pintype "passive"))
      (node (ref "R014") (pin "2") (pinfunction "2_2") (pintype "passive"))
      (node (ref "SJ9") (pin "1") (pinfunction "1_1") (pintype "passive"))
      (node (ref "U101") (pin "20") (pinfunction "VDD_20") (pintype "power_in"))
      (node (ref "U201") (pin "1") (pinfunction "EN_1") (pintype "input"))
      (node (ref "U201") (pin "2") (pinfunction "IN_2") (pintype "input"))
    )
    (net (code "57") (name "GND") (class "Default")
      (node (ref "C002") (pin "2") (pinfunction "2_2") (pintype "passive"))
      (node (ref "C120") (pin "1") (pinfunction "1_1") (pintype "passive"))
      (node (ref "C201") (pin "2") (pinfunction "2_2") (pintype "passive"))
      (node (ref "C202") (pin "2") (pinfunction "2_2") (pintype "passive"))
      (node (ref "C203") (pin "2") (pinfunction "2_2") (pintype "passive"))
      (node (ref "C407") (pin "2") (pinfunction "2_2") (pintype "passive"))
      (node (ref "C423") (pin "2") (pinfunction "2_2") (pintype "passive"))
      (node (ref "C443") (pin "2") (pinfunction "2_2") (pintype "passive"))
      (node (ref "C451") (pin "2") (pinfunction "2_2") (pintype "passive"))
      (node (ref "C461") (pin "1") (pinfunction "1_1") (pintype "passive"))
      (node (ref "C462") (pin "1") (pinfunction "1_1") (pintype "passive"))
      (node (ref "C463") (pin "2") (pinfunction "2_2") (pintype "passive"))
      (node (ref "J002") (pin "5") (pinfunction "5_5") (pintype "passive"))
      (node (ref "J403") (pin "1") (pinfunction "GND1_1") (pintype "bidirectional"))
      (node (ref "J403") (pin "5") (pinfunction "GND2_5") (pintype "bidirectional"))
      (node (ref "R014") (pin "1") (pinfunction "1_1") (pintype "passive"))
      (node (ref "SJ1") (pin "1") (pinfunction "1_1") (pintype "passive"))
      (node (ref "SJ10") (pin "1") (pinfunction "1_1") (pintype "passive"))
      (node (ref "SJ11") (pin "1") (pinfunction "1_1") (pintype "passive"))
      (node (ref "SJ2") (pin "1") (pinfunction "1_1") (pintype "passive"))
      (node (ref "SJ3") (pin "1") (pinfunction "1_1") (pintype "passive"))
      (node (ref "SJ4") (pin "1") (pinfunction "1_1") (pintype "passive"))
      (node (ref "SJ5") (pin "1") (pinfunction "1_1") (pintype "passive"))
      (node (ref "SJ6") (pin "1") (pinfunction "1_1") (pintype "passive"))
      (node (ref "SJ7") (pin "1") (pinfunction "1_1") (pintype "passive"))
      (node (ref "SJ8") (pin "1") (pinfunction "1_1") (pintype "passive"))
      (node (ref "U101") (pin "19") (pinfunction "VSS_19") (pintype "power_in"))
      (node (ref "U101") (pin "8") (pinfunction "VSS_8") (pintype "power_in"))
      (node (ref "U201") (pin "5") (pinfunction "GND_5") (pintype "power_in"))
      (node (ref "U201") (pin "6") (pinfunction "GND_6") (pintype "power_in"))
      (node (ref "U201") (pin "7") (pinfunction "GND_7") (pintype "power_in"))
      (node (ref "U201") (pin "8") (pinfunction "GND_8") (pintype "power_in"))
      (node (ref "U401") (pin "18") (pinfunction "VSS_18") (pintype "power_in"))
      (node (ref "U401") (pin "25") (pinfunction "VSS_25") (pintype "power_in"))
      (node (ref "U401") (pin "42") (pinfunction "VSS_42") (pintype "power_in"))
      (node (ref "U401") (pin "50") (pinfunction "VSS_50") (pintype "power_in"))
      (node (ref "U401") (pin "59") (pinfunction "VSSA_59") (pintype "power_in"))
      (node (ref "U401") (pin "6") (pinfunction "VSS_6") (pintype "power_in"))
      (node (ref "Y401") (pin "2") (pinfunction "1_2") (pintype "bidirectional"))
      (node (ref "Y401") (pin "4") (pinfunction "1_4") (pintype "bidirectional"))
    )
    (net (code "58") (name "Net-(U201A-BYP)") (class "Default")
      (node (ref "C203") (pin "1") (pinfunction "1_1") (pintype "passive"))
      (node (ref "U201") (pin "4") (pinfunction "BYP_4") (pintype "passive"))
    )
    (net (code "59") (name "Net-(U201A-OUT)") (class "Default")
      (node (ref "C202") (pin "1") (pinfunction "1_1") (pintype "passive"))
      (node (ref "U201") (pin "3") (pinfunction "OUT_3") (pintype "output"))
    )
    (net (code "60") (name "Net-(U401-XTAL1)") (class "Default")
      (node (ref "C462") (pin "2") (pinfunction "2_2") (pintype "passive"))
      (node (ref "U401") (pin "62") (pinfunction "XTAL1_62") (pintype "input"))
      (node (ref "Y401") (pin "3") (pinfunction "2_3") (pintype "passive"))
    )
    (net (code "61") (name "Net-(U401-XTAL2)") (class "Default")
      (node (ref "C461") (pin "2") (pinfunction "2_2") (pintype "passive"))
      (node (ref "U401") (pin "61") (pinfunction "XTAL2_61") (pintype "output"))
      (node (ref "Y401") (pin "1") (pinfunction "1_1") (pintype "passive"))
    )
    (net (code "62") (name "VCC") (class "Default")
      (node (ref "C407") (pin "1") (pinfunction "1_1") (pintype "passive"))
      (node (ref "C423") (pin "1") (pinfunction "1_1") (pintype "passive"))
      (node (ref "C443") (pin "1") (pinfunction "1_1") (pintype "passive"))
      (node (ref "C451") (pin "1") (pinfunction "1_1") (pintype "passive"))
      (node (ref "C463") (pin "1") (pinfunction "1_1") (pintype "passive"))
      (node (ref "J002") (pin "6") (pinfunction "6_6") (pintype "passive"))
      (node (ref "J403") (pin "2") (pinfunction "VCC_2") (pintype "bidirectional"))
      (node (ref "R441") (pin "2") (pinfunction "2_2") (pintype "passive"))
      (node (ref "R457") (pin "2") (pinfunction "2_2") (pintype "passive"))
      (node (ref "U401") (pin "23") (pinfunction "VDD3-1_23") (pintype "power_in"))
      (node (ref "U401") (pin "3") (pinfunction "RTXC1_3") (pintype "input"))
      (node (ref "U401") (pin "43") (pinfunction "VDD3-2_43") (pintype "power_in"))
      (node (ref "U401") (pin "49") (pinfunction "VBAT_49") (pintype "power_in"))
      (node (ref "U401") (pin "51") (pinfunction "VDD3-3_51") (pintype "power_in"))
      (node (ref "U401") (pin "63") (pinfunction "VREF_63") (pintype "input"))
      (node (ref "U401") (pin "7") (pinfunction "VDDA3_7") (pintype "power_in"))
    )
    (net (code "63") (name "unconnected-(J002-Pad7)") (class "Default")
      (node (ref "J002") (pin "7") (pinfunction "7_7") (pintype "passive"))
    )
    (net (code "64") (name "unconnected-(J002-Pad8)") (class "Default")
      (node (ref "J002") (pin "8") (pinfunction "8_8") (pintype "passive"))
    )
    (net (code "65") (name "unconnected-(U101-COM2{slash}DACOUT{slash}VREF-{slash}C2IN+{slash}AN2{slash}RA2-Pad4)") (class "Default")
      (node (ref "U101") (pin "4") (pinfunction "COM2/DACOUT/VREF-/C2IN+/AN2/RA2_4") (pintype "bidirectional"))
    )
    (net (code "66") (name "unconnected-(U101-SEG7{slash}C12IN1-{slash}AN1{slash}RA1-Pad3)") (class "Default")
      (node (ref "U101") (pin "3") (pinfunction "SEG7/C12IN1-/AN1/RA1_3") (pintype "bidirectional"))
    )
    (net (code "67") (name "unconnected-(U101-SEG12{slash}VCAP{slash}SS{slash}SRNQ{slash}C2OUT{slash}C12IN0-{slash}AN0{slash}RA0-Pad2)") (class "Default")
      (node (ref "U101") (pin "2") (pinfunction "SEG12/VCAP/SS/SRNQ/C2OUT/C12IN0-/AN0/RA0_2") (pintype "bidirectional"))
    )
    (net (code "68") (name "unconnected-(U101-SEG15{slash}COM3{slash}VREF+{slash}C1IN+{slash}AN3{slash}RA3-Pad5)") (class "Default")
      (node (ref "U101") (pin "5") (pinfunction "SEG15/COM3/VREF+/C1IN+/AN3/RA3_5") (pintype "bidirectional"))
    )
    (net (code "69") (name "unconnected-(U401-(AD0.1{slash}CAP0.2{slash}MAT0.2)P0.28-Pad13)") (class "Default")
      (node (ref "U401") (pin "13") (pinfunction "(AD0.1/CAP0.2/MAT0.2)P0.28_13") (pintype "bidirectional"))
    )
    (net (code "70") (name "unconnected-(U401-(AD0.2{slash}CAP0.3{slash}MAT0.3)P0.29-Pad14)") (class "Default")
      (node (ref "U401") (pin "14") (pinfunction "(AD0.2/CAP0.3/MAT0.3)P0.29_14") (pintype "bidirectional"))
    )
    (net (code "71") (name "unconnected-(U401-(AD0.3{slash}EINT3{slash}CAP0.0)P0.30-Pad15)") (class "Default")
      (node (ref "U401") (pin "15") (pinfunction "(AD0.3/EINT3/CAP0.0)P0.30_15") (pintype "bidirectional"))
    )
    (net (code "72") (name "unconnected-(U401-(AD0.4{slash}AOUT)P0.25-Pad9)") (class "Default")
      (node (ref "U401") (pin "9") (pinfunction "(AD0.4/AOUT)P0.25_9") (pintype "bidirectional"))
    )
    (net (code "73") (name "unconnected-(U401-(AD1.7{slash}CAP0.0{slash}MAT0.0)P0.22-Pad2)") (class "Default")
      (node (ref "U401") (pin "2") (pinfunction "(AD1.7/CAP0.0/MAT0.0)P0.22_2") (pintype "bidirectional"))
    )
    (net (code "74") (name "unconnected-(U401-(MAT1.2{slash}MOSI1{slash}CAP1.2)P0.19-Pad54)") (class "Default")
      (node (ref "U401") (pin "54") (pinfunction "(MAT1.2/MOSI1/CAP1.2)P0.19_54") (pintype "bidirectional"))
    )
    (net (code "75") (name "unconnected-(U401-(MAT1.3{slash}SSEL1{slash}EINT3)P0.20-Pad55)") (class "Default")
      (node (ref "U401") (pin "55") (pinfunction "(MAT1.3/SSEL1/EINT3)P0.20_55") (pintype "bidirectional"))
    )
    (net (code "76") (name "unconnected-(U401-(PWM5{slash}AD1.6{slash}CAP1.3)P0.21-Pad1)") (class "Default")
      (node (ref "U401") (pin "1") (pinfunction "(PWM5/AD1.6/CAP1.3)P0.21_1") (pintype "bidirectional"))
    )
    (net (code "77") (name "unconnected-(U401-(RI1{slash}EINT2{slash}AD1.5)P0.15-Pad45)") (class "Default")
      (node (ref "U401") (pin "45") (pinfunction "(RI1/EINT2/AD1.5)P0.15_45") (pintype "bidirectional"))
    )
    (net (code "78") (name "unconnected-(U401-P1.16(TRACEPKT0)-Pad16)") (class "Default")
      (node (ref "U401") (pin "16") (pinfunction "P1.16(TRACEPKT0)_16") (pintype "bidirectional"))
    )
    (net (code "79") (name "unconnected-(U401-P1.17(TRACEPKT1)-Pad12)") (class "Default")
      (node (ref "U401") (pin "12") (pinfunction "P1.17(TRACEPKT1)_12") (pintype "bidirectional"))
    )
    (net (code "80") (name "unconnected-(U401-P1.18(TRACEPKT2)-Pad8)") (class "Default")
      (node (ref "U401") (pin "8") (pinfunction "P1.18(TRACEPKT2)_8") (pintype "bidirectional"))
    )
    (net (code "81") (name "unconnected-(U401-P1.19(TRACEPKT3)-Pad4)") (class "Default")
      (node (ref "U401") (pin "4") (pinfunction "P1.19(TRACEPKT3)_4") (pintype "bidirectional"))
    )
    (net (code "82") (name "unconnected-(U401-P1.20(TRACESYNC)-Pad48)") (class "Default")
      (node (ref "U401") (pin "48") (pinfunction "P1.20(TRACESYNC)_48") (pintype "bidirectional"))
    )
    (net (code "83") (name "unconnected-(U401-P1.21(PIPESTAT0)-Pad44)") (class "Default")
      (node (ref "U401") (pin "44") (pinfunction "P1.21(PIPESTAT0)_44") (pintype "bidirectional"))
    )
    (net (code "84") (name "unconnected-(U401-P1.22(PIPESTAT1)-Pad40)") (class "Default")
      (node (ref "U401") (pin "40") (pinfunction "P1.22(PIPESTAT1)_40") (pintype "bidirectional"))
    )
    (net (code "85") (name "unconnected-(U401-P1.23(PIPESTAT2)-Pad36)") (class "Default")
      (node (ref "U401") (pin "36") (pinfunction "P1.23(PIPESTAT2)_36") (pintype "bidirectional"))
    )
    (net (code "86") (name "unconnected-(U401-P1.24(TRACECLK)-Pad32)") (class "Default")
      (node (ref "U401") (pin "32") (pinfunction "P1.24(TRACECLK)_32") (pintype "bidirectional"))
    )
    (net (code "87") (name "unconnected-(U401-P1.25(EXTIN0)-Pad28)") (class "Default")
      (node (ref "U401") (pin "28") (pinfunction "P1.25(EXTIN0)_28") (pintype "bidirectional"))
    )
    (net (code "88") (name "unconnected-(U401-P1.26(RTCK)-Pad24)") (class "Default")
      (node (ref "U401") (pin "24") (pinfunction "P1.26(RTCK)_24") (pintype "bidirectional"))
    )
    (net (code "89") (name "unconnected-(U401-P1.27(TDO)-Pad64)") (class "Default")
      (node (ref "U401") (pin "64") (pinfunction "P1.27(TDO)_64") (pintype "bidirectional"))
    )
    (net (code "90") (name "unconnected-(U401-P1.28(TDI)-Pad60)") (class "Default")
      (node (ref "U401") (pin "60") (pinfunction "P1.28(TDI)_60") (pintype "bidirectional"))
    )
    (net (code "91") (name "unconnected-(U401-P1.29(TCK)-Pad56)") (class "Default")
      (node (ref "U401") (pin "56") (pinfunction "P1.29(TCK)_56") (pintype "bidirectional"))
    )
    (net (code "92") (name "unconnected-(U401-P1.30(TMS)-Pad52)") (class "Default")
      (node (ref "U401") (pin "52") (pinfunction "P1.30(TMS)_52") (pintype "bidirectional"))
    )
    (net (code "93") (name "unconnected-(U401-P1.31({slash}TRST)-Pad20)") (class "Default")
      (node (ref "U401") (pin "20") (pinfunction "P1.31(/TRST)_20") (pintype "bidirectional"))
    )
    (net (code "94") (name "unconnected-(U401-RTXC2-Pad5)") (class "Default")
      (node (ref "U401") (pin "5") (pinfunction "RTXC2_5") (pintype "output"))
    )
  )
)
